# TRC_ESP8266.net
KiCad netlist of a schematic drawn in EasyEDA
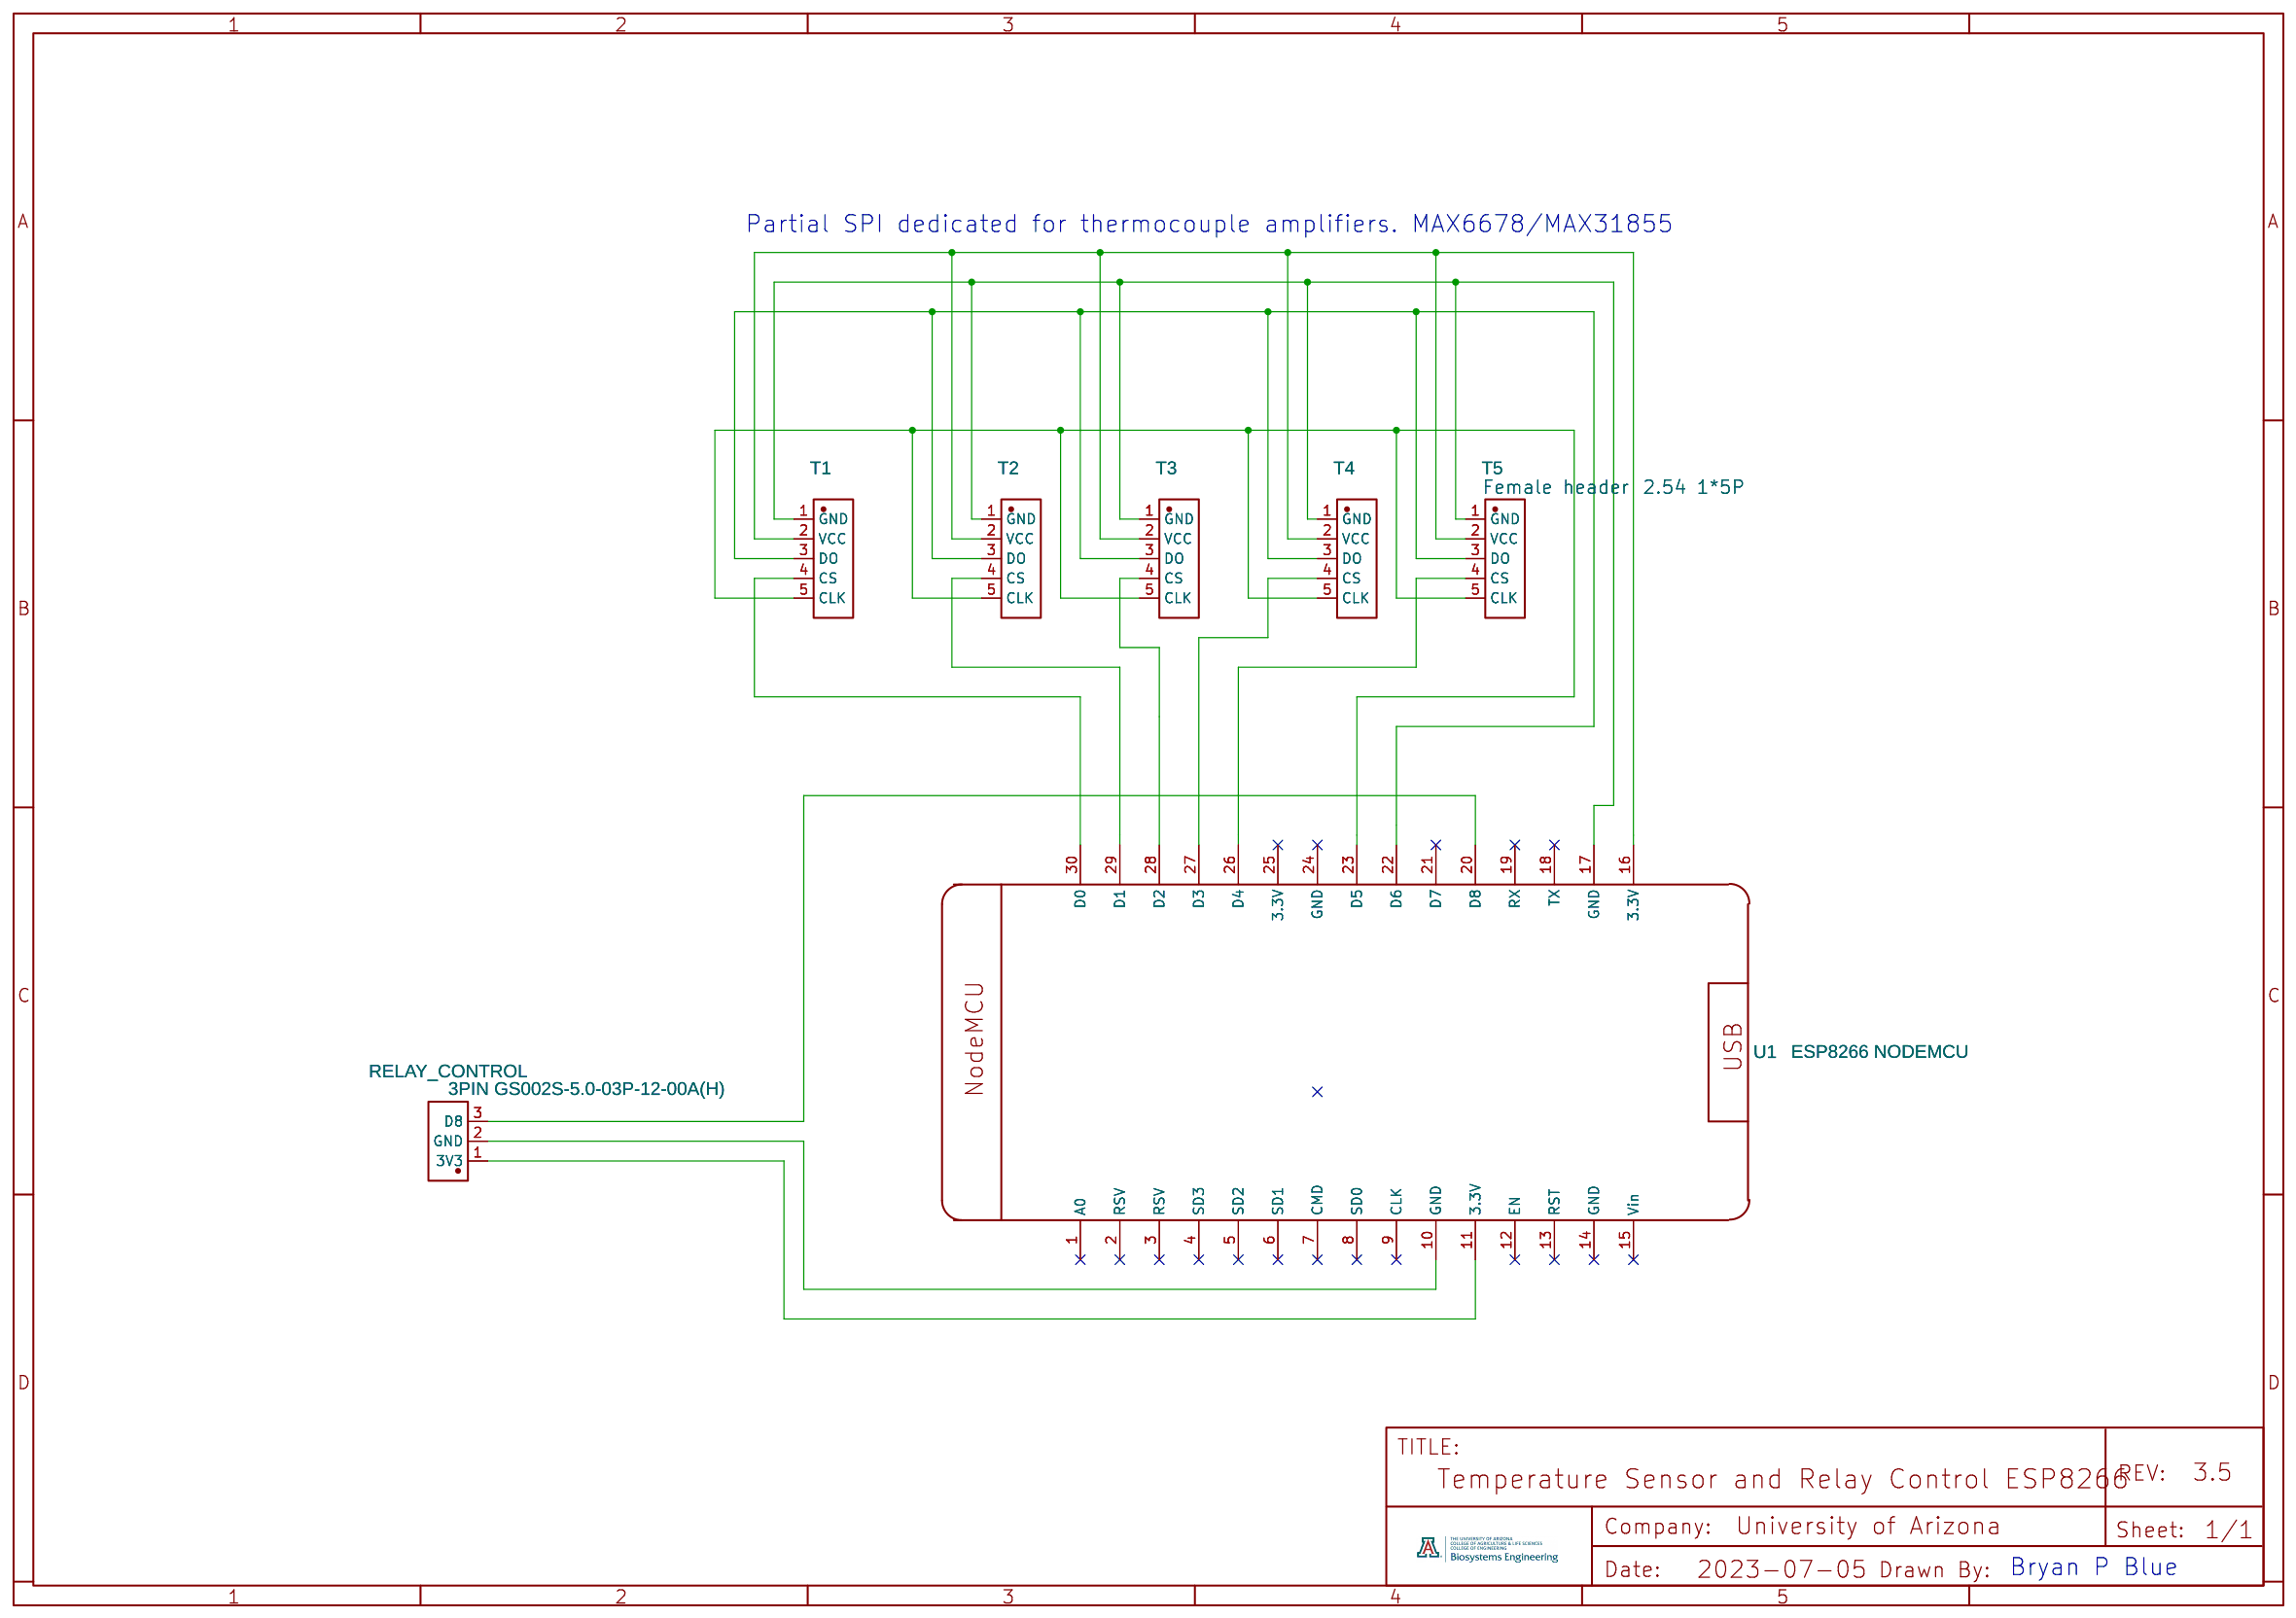
[diagram p0: schematic sheet]

(export (version "E")
  (design (tool "Eeschema 10.0.6"))
  (components
    (comp (ref "RELAY_CONTROL")
      (value "3PIN GS002S-5.0-03P-12-00A(H)")
      (fields
        (field (name "BOM_Manufacturer Part") "GS002S-5.0-03P-12-00A(H)")
        (field (name "BOM_Supplier Part") "C5142592")
      )
      (libsource (lib "") (part "3PIN клеммник винтовой GS002S-5.0-03P-12-00A(H)"))
    )
    (comp (ref "T1")
      (value "Female header　2.54 1*5Ｐ")
      (fields (field (name "BOM_Supplier Part") "C46341"))
      (libsource (lib "") (part "Female header　2.54 1*5Ｐ"))
    )
    (comp (ref "T2")
      (value "Female header　2.54 1*5Ｐ")
      (fields (field (name "BOM_Supplier Part") "C46341"))
      (libsource (lib "") (part "Female header　2.54 1*5Ｐ"))
    )
    (comp (ref "T3")
      (value "Female header　2.54 1*5Ｐ")
      (fields (field (name "BOM_Supplier Part") "C46341"))
      (libsource (lib "") (part "Female header　2.54 1*5Ｐ"))
    )
    (comp (ref "T4")
      (value "Female header　2.54 1*5Ｐ")
      (fields (field (name "BOM_Supplier Part") "C46341"))
      (libsource (lib "") (part "Female header　2.54 1*5Ｐ"))
    )
    (comp (ref "T5")
      (value "Female header　2.54 1*5Ｐ")
      (fields (field (name "BOM_Supplier Part") "C46341"))
      (libsource (lib "") (part "Female header　2.54 1*5Ｐ"))
    )
    (comp (ref "U1") (value "ESP8266 NODEMCU") (libsource (lib "") (part "NODEMCU COPY")))
  )
  (nets
    (net (code "1") (name "Net-(RELAY_CONTROL-3V3)") (class "Default")
      (node (ref "RELAY_CONTROL") (pin "1") (pinfunction "3V3_1") (pintype "unspecified"))
      (node (ref "U1") (pin "11") (pinfunction "3.3V_11") (pintype "passive"))
    )
    (net (code "2") (name "Net-(RELAY_CONTROL-D8)") (class "Default")
      (node (ref "RELAY_CONTROL") (pin "3") (pinfunction "D8_3") (pintype "unspecified"))
      (node (ref "U1") (pin "20") (pinfunction "D8_20") (pintype "unspecified"))
    )
    (net (code "3") (name "Net-(RELAY_CONTROL-GND)") (class "Default")
      (node (ref "RELAY_CONTROL") (pin "2") (pinfunction "GND_2") (pintype "unspecified"))
      (node (ref "U1") (pin "10") (pinfunction "GND_10") (pintype "passive"))
    )
    (net (code "4") (name "Net-(T1-CLK)") (class "Default")
      (node (ref "T1") (pin "5") (pinfunction "CLK_5") (pintype "input"))
      (node (ref "T2") (pin "5") (pinfunction "CLK_5") (pintype "input"))
      (node (ref "T3") (pin "5") (pinfunction "CLK_5") (pintype "input"))
      (node (ref "T4") (pin "5") (pinfunction "CLK_5") (pintype "input"))
      (node (ref "T5") (pin "5") (pinfunction "CLK_5") (pintype "input"))
      (node (ref "U1") (pin "23") (pinfunction "D5_23") (pintype "unspecified"))
    )
    (net (code "5") (name "Net-(T1-CS)") (class "Default")
      (node (ref "T1") (pin "4") (pinfunction "CS_4") (pintype "input"))
      (node (ref "U1") (pin "30") (pinfunction "D0_30") (pintype "unspecified"))
    )
    (net (code "6") (name "Net-(T1-DO)") (class "Default")
      (node (ref "T1") (pin "3") (pinfunction "DO_3") (pintype "output"))
      (node (ref "T2") (pin "3") (pinfunction "DO_3") (pintype "output"))
      (node (ref "T3") (pin "3") (pinfunction "DO_3") (pintype "output"))
      (node (ref "T4") (pin "3") (pinfunction "DO_3") (pintype "output"))
      (node (ref "T5") (pin "3") (pinfunction "DO_3") (pintype "output"))
      (node (ref "U1") (pin "22") (pinfunction "D6_22") (pintype "unspecified"))
    )
    (net (code "7") (name "Net-(T1-GND)") (class "Default")
      (node (ref "T1") (pin "1") (pinfunction "GND_1") (pintype "passive"))
      (node (ref "T2") (pin "1") (pinfunction "GND_1") (pintype "passive"))
      (node (ref "T3") (pin "1") (pinfunction "GND_1") (pintype "passive"))
      (node (ref "T4") (pin "1") (pinfunction "GND_1") (pintype "passive"))
      (node (ref "T5") (pin "1") (pinfunction "GND_1") (pintype "passive"))
      (node (ref "U1") (pin "17") (pinfunction "GND_17") (pintype "passive"))
    )
    (net (code "8") (name "Net-(T1-VCC)") (class "Default")
      (node (ref "T1") (pin "2") (pinfunction "VCC_2") (pintype "passive"))
      (node (ref "T2") (pin "2") (pinfunction "VCC_2") (pintype "passive"))
      (node (ref "T3") (pin "2") (pinfunction "VCC_2") (pintype "passive"))
      (node (ref "T4") (pin "2") (pinfunction "VCC_2") (pintype "passive"))
      (node (ref "T5") (pin "2") (pinfunction "VCC_2") (pintype "passive"))
      (node (ref "U1") (pin "16") (pinfunction "3.3V_16") (pintype "passive"))
    )
    (net (code "9") (name "Net-(T2-CS)") (class "Default")
      (node (ref "T2") (pin "4") (pinfunction "CS_4") (pintype "input"))
      (node (ref "U1") (pin "29") (pinfunction "D1_29") (pintype "unspecified"))
    )
    (net (code "10") (name "Net-(T3-CS)") (class "Default")
      (node (ref "T3") (pin "4") (pinfunction "CS_4") (pintype "input"))
      (node (ref "U1") (pin "28") (pinfunction "D2_28") (pintype "unspecified"))
    )
    (net (code "11") (name "Net-(T4-CS)") (class "Default")
      (node (ref "T4") (pin "4") (pinfunction "CS_4") (pintype "input"))
      (node (ref "U1") (pin "27") (pinfunction "D3_27") (pintype "unspecified"))
    )
    (net (code "12") (name "Net-(T5-CS)") (class "Default")
      (node (ref "T5") (pin "4") (pinfunction "CS_4") (pintype "input"))
      (node (ref "U1") (pin "26") (pinfunction "D4_26") (pintype "unspecified"))
    )
    (net (code "13") (name "unconnected-(U1-3.3V-Pad25)") (class "Default")
      (node (ref "U1") (pin "25") (pinfunction "3.3V_25") (pintype "passive+no_connect"))
    )
    (net (code "14") (name "unconnected-(U1-A0-Pad1)") (class "Default")
      (node (ref "U1") (pin "1") (pinfunction "A0_1") (pintype "unspecified+no_connect"))
    )
    (net (code "15") (name "unconnected-(U1-CLK-Pad9)") (class "Default")
      (node (ref "U1") (pin "9") (pinfunction "CLK_9") (pintype "output+no_connect"))
    )
    (net (code "16") (name "unconnected-(U1-CMD-Pad7)") (class "Default")
      (node (ref "U1") (pin "7") (pinfunction "CMD_7") (pintype "unspecified+no_connect"))
    )
    (net (code "17") (name "unconnected-(U1-D7-Pad21)") (class "Default")
      (node (ref "U1") (pin "21") (pinfunction "D7_21") (pintype "unspecified+no_connect"))
    )
    (net (code "18") (name "unconnected-(U1-EN-Pad12)") (class "Default")
      (node (ref "U1") (pin "12") (pinfunction "EN_12") (pintype "unspecified+no_connect"))
    )
    (net (code "19") (name "unconnected-(U1-GND-Pad14)") (class "Default")
      (node (ref "U1") (pin "14") (pinfunction "GND_14") (pintype "passive+no_connect"))
    )
    (net (code "20") (name "unconnected-(U1-GND-Pad24)") (class "Default")
      (node (ref "U1") (pin "24") (pinfunction "GND_24") (pintype "passive+no_connect"))
    )
    (net (code "21") (name "unconnected-(U1-RST-Pad13)") (class "Default")
      (node (ref "U1") (pin "13") (pinfunction "RST_13") (pintype "unspecified+no_connect"))
    )
    (net (code "22") (name "unconnected-(U1-RSV-Pad2)") (class "Default")
      (node (ref "U1") (pin "2") (pinfunction "RSV_2") (pintype "unspecified+no_connect"))
    )
    (net (code "23") (name "unconnected-(U1-RSV-Pad3)") (class "Default")
      (node (ref "U1") (pin "3") (pinfunction "RSV_3") (pintype "unspecified+no_connect"))
    )
    (net (code "24") (name "unconnected-(U1-RX-Pad19)") (class "Default")
      (node (ref "U1") (pin "19") (pinfunction "RX_19") (pintype "unspecified+no_connect"))
    )
    (net (code "25") (name "unconnected-(U1-SD0-Pad8)") (class "Default")
      (node (ref "U1") (pin "8") (pinfunction "SD0_8") (pintype "unspecified+no_connect"))
    )
    (net (code "26") (name "unconnected-(U1-SD1-Pad6)") (class "Default")
      (node (ref "U1") (pin "6") (pinfunction "SD1_6") (pintype "unspecified+no_connect"))
    )
    (net (code "27") (name "unconnected-(U1-SD2-Pad5)") (class "Default")
      (node (ref "U1") (pin "5") (pinfunction "SD2_5") (pintype "unspecified+no_connect"))
    )
    (net (code "28") (name "unconnected-(U1-SD3-Pad4)") (class "Default")
      (node (ref "U1") (pin "4") (pinfunction "SD3_4") (pintype "unspecified+no_connect"))
    )
    (net (code "29") (name "unconnected-(U1-TX-Pad18)") (class "Default")
      (node (ref "U1") (pin "18") (pinfunction "TX_18") (pintype "unspecified+no_connect"))
    )
    (net (code "30") (name "unconnected-(U1-Vin-Pad15)") (class "Default")
      (node (ref "U1") (pin "15") (pinfunction "Vin_15") (pintype "passive+no_connect"))
    )
  )
)
